# MCU_Power.net
KiCad netlist of a schematic drawn in Altium Designer
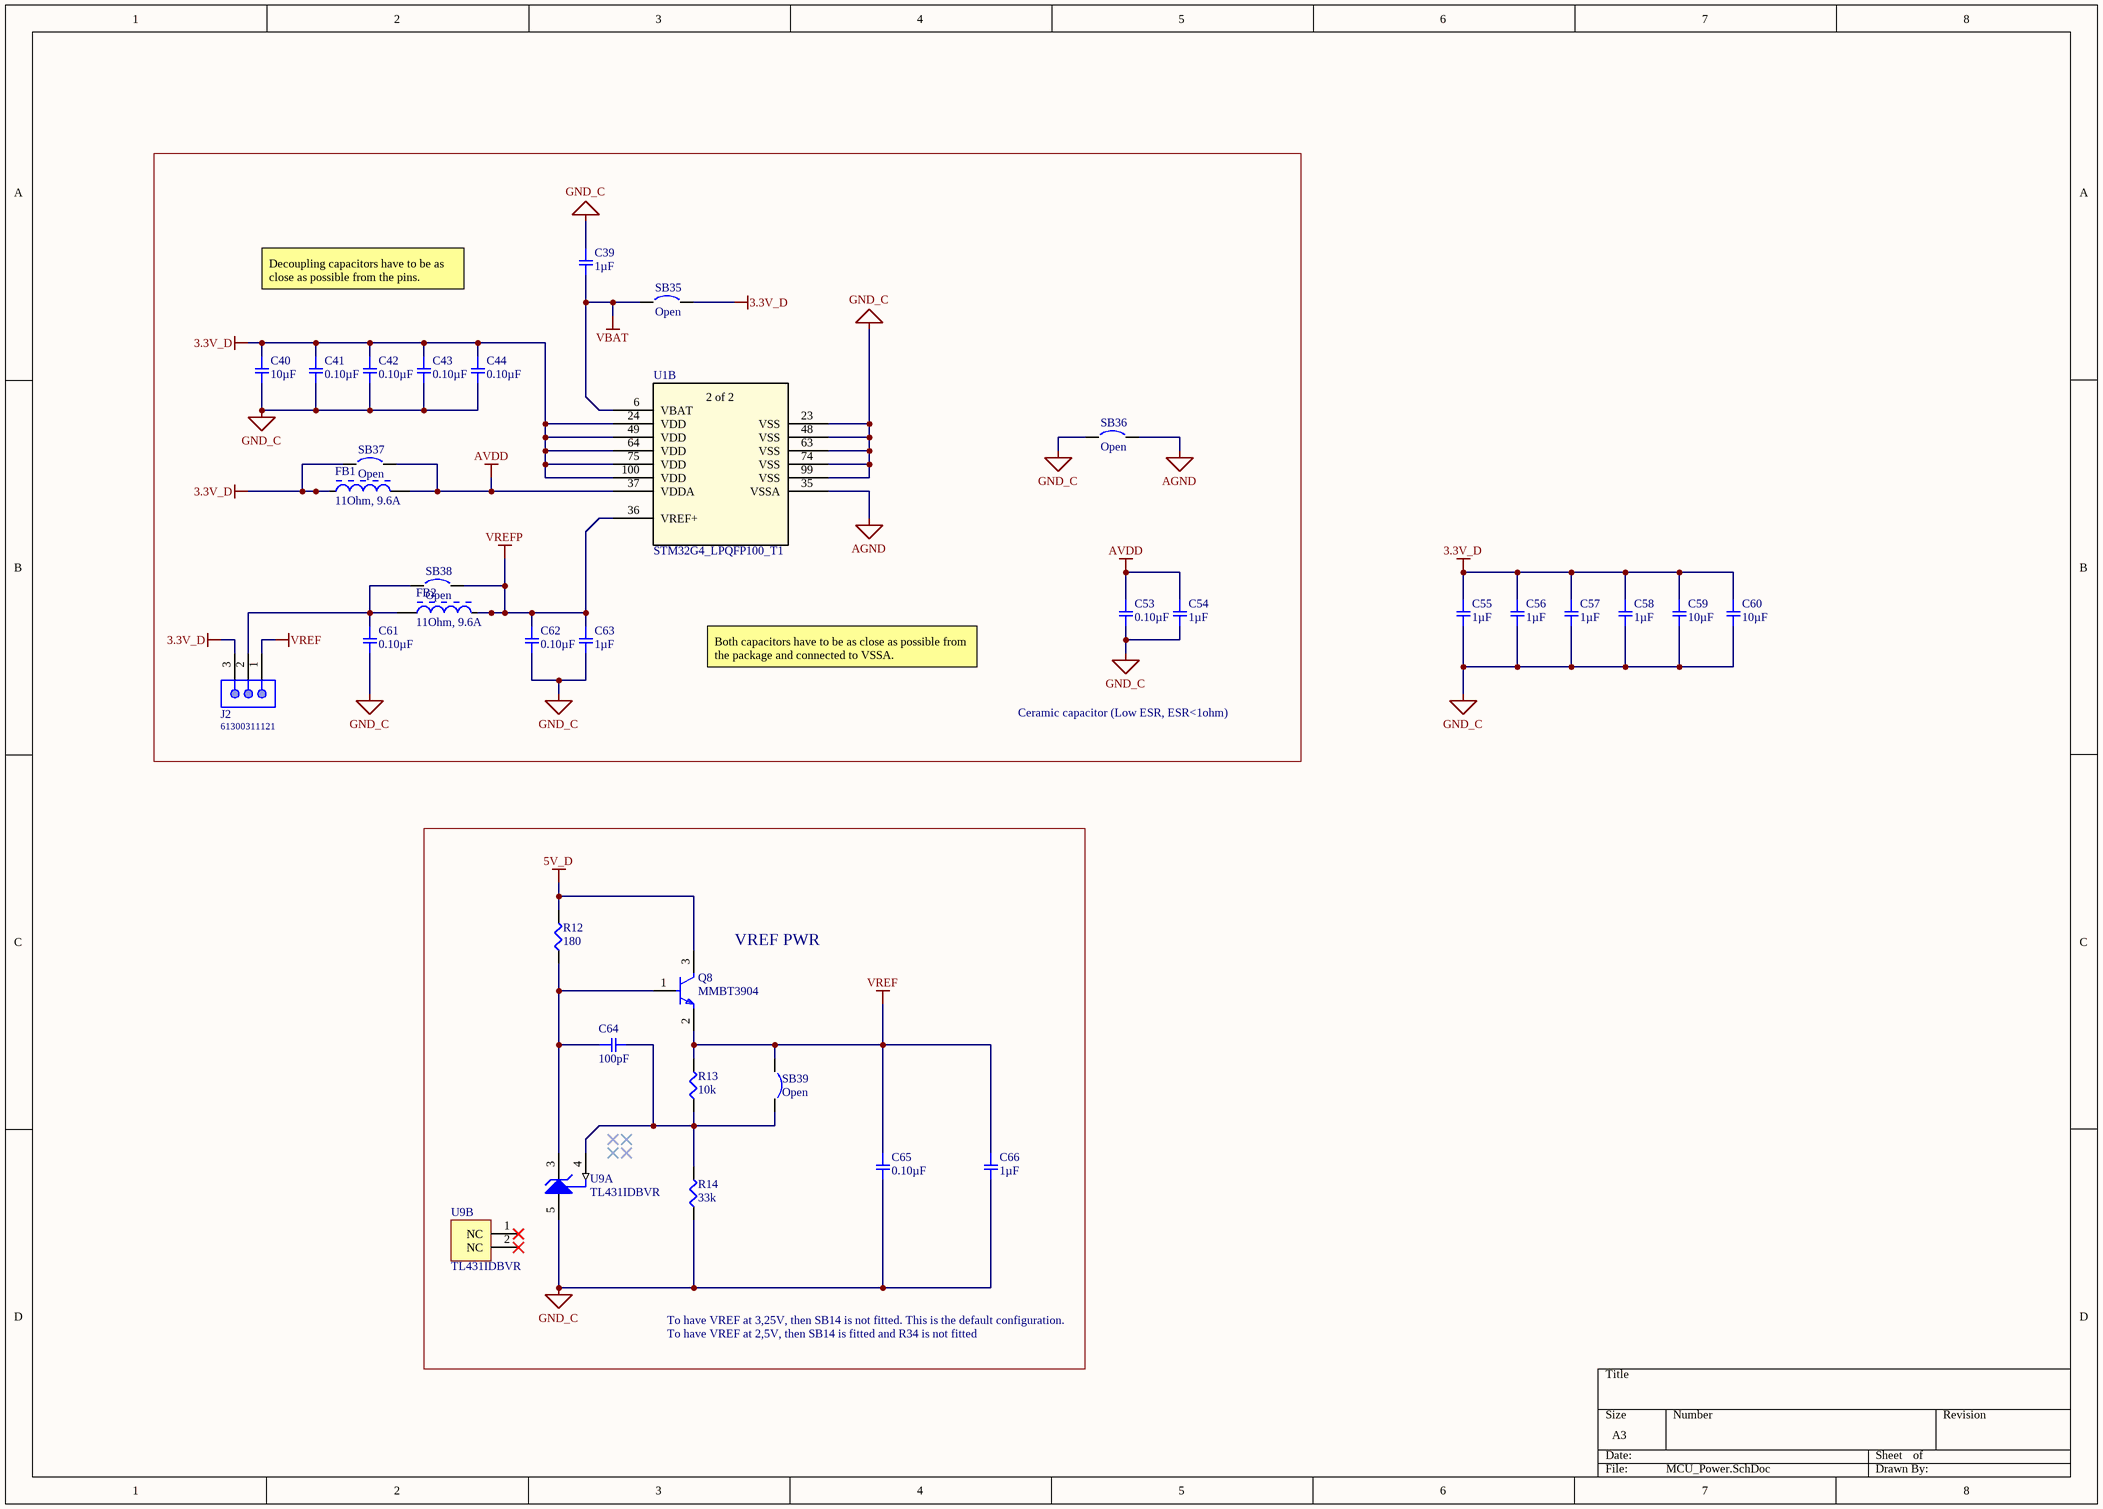
[diagram p0: MCU_Power.SchDoc]

(export (version "E")
  (design (tool "Eeschema 10.0.6"))
  (components
    (comp (ref "C39")
      (value "1µF")
      (footprint "SMD-0805C")
      (description "CAP CER 1UF 16V X7R 0805")
      (fields
        (field (name "DIGI-KEY PART NUMBER") "490-8043-1-ND")
        (field (name "PART NUMBER") "GCM219R71C105KA37D")
      )
      (libsource (lib "capacitor_murata_0805") (part "GCM219R71C105KA37D"))
    )
    (comp (ref "C40")
      (value "10µF")
      (footprint "SMD-0805C")
      (description "CAP CER 10UF 10V X7R 0805")
      (fields
        (field (name "DIGI-KEY PART NUMBER") "490-10674-1-ND")
        (field (name "PART NUMBER") "GCM21BR71A106KE22L")
      )
      (libsource (lib "capacitor_murata_0805") (part "GCM21BR71A106KE22L"))
    )
    (comp (ref "C41")
      (value "0.10µF")
      (footprint "SMD-0805C")
      (description "CAP CER 0.1UF 100V X7R 0805")
      (fields
        (field (name "DIGI-KEY PART NUMBER") "490-5825-1-ND")
        (field (name "PART NUMBER") "GCJ21BR72A104KA01L")
      )
      (libsource (lib "capacitor_murata_0805") (part "GCJ21BR72A104KA01L"))
    )
    (comp (ref "C42")
      (value "0.10µF")
      (footprint "SMD-0805C")
      (description "CAP CER 0.1UF 100V X7R 0805")
      (fields
        (field (name "DIGI-KEY PART NUMBER") "490-5825-1-ND")
        (field (name "PART NUMBER") "GCJ21BR72A104KA01L")
      )
      (libsource (lib "capacitor_murata_0805") (part "GCJ21BR72A104KA01L"))
    )
    (comp (ref "C43")
      (value "0.10µF")
      (footprint "SMD-0805C")
      (description "CAP CER 0.1UF 100V X7R 0805")
      (fields
        (field (name "DIGI-KEY PART NUMBER") "490-5825-1-ND")
        (field (name "PART NUMBER") "GCJ21BR72A104KA01L")
      )
      (libsource (lib "capacitor_murata_0805") (part "GCJ21BR72A104KA01L"))
    )
    (comp (ref "C44")
      (value "0.10µF")
      (footprint "SMD-0805C")
      (description "CAP CER 0.1UF 100V X7R 0805")
      (fields
        (field (name "DIGI-KEY PART NUMBER") "490-5825-1-ND")
        (field (name "PART NUMBER") "GCJ21BR72A104KA01L")
      )
      (libsource (lib "capacitor_murata_0805") (part "GCJ21BR72A104KA01L"))
    )
    (comp (ref "C53")
      (value "0.10µF")
      (footprint "SMD-0805C")
      (description "CAP CER 0.1UF 100V X7R 0805")
      (fields
        (field (name "DIGI-KEY PART NUMBER") "490-5825-1-ND")
        (field (name "PART NUMBER") "GCJ21BR72A104KA01L")
      )
      (libsource (lib "capacitor_murata_0805") (part "GCJ21BR72A104KA01L"))
    )
    (comp (ref "C54")
      (value "1µF")
      (footprint "SMD-0805C")
      (description "CAP CER 1UF 16V X7R 0805")
      (fields
        (field (name "DIGI-KEY PART NUMBER") "490-8043-1-ND")
        (field (name "PART NUMBER") "GCM219R71C105KA37D")
      )
      (libsource (lib "capacitor_murata_0805") (part "GCM219R71C105KA37D"))
    )
    (comp (ref "C55")
      (value "1µF")
      (footprint "SMD-0805C")
      (description "CAP CER 1UF 16V X7R 0805")
      (fields
        (field (name "DIGI-KEY PART NUMBER") "490-8043-1-ND")
        (field (name "PART NUMBER") "GCM219R71C105KA37D")
      )
      (libsource (lib "capacitor_murata_0805") (part "GCM219R71C105KA37D"))
    )
    (comp (ref "C56")
      (value "1µF")
      (footprint "SMD-0805C")
      (description "CAP CER 1UF 16V X7R 0805")
      (fields
        (field (name "DIGI-KEY PART NUMBER") "490-8043-1-ND")
        (field (name "PART NUMBER") "GCM219R71C105KA37D")
      )
      (libsource (lib "capacitor_murata_0805") (part "GCM219R71C105KA37D"))
    )
    (comp (ref "C57")
      (value "1µF")
      (footprint "SMD-0805C")
      (description "CAP CER 1UF 16V X7R 0805")
      (fields
        (field (name "DIGI-KEY PART NUMBER") "490-8043-1-ND")
        (field (name "PART NUMBER") "GCM219R71C105KA37D")
      )
      (libsource (lib "capacitor_murata_0805") (part "GCM219R71C105KA37D"))
    )
    (comp (ref "C58")
      (value "1µF")
      (footprint "SMD-0805C")
      (description "CAP CER 1UF 16V X7R 0805")
      (fields
        (field (name "DIGI-KEY PART NUMBER") "490-8043-1-ND")
        (field (name "PART NUMBER") "GCM219R71C105KA37D")
      )
      (libsource (lib "capacitor_murata_0805") (part "GCM219R71C105KA37D"))
    )
    (comp (ref "C59")
      (value "10µF")
      (footprint "SMD-0805C")
      (description "CAP CER 10UF 10V X7R 0805")
      (fields
        (field (name "DIGI-KEY PART NUMBER") "490-10674-1-ND")
        (field (name "PART NUMBER") "GCM21BR71A106KE22L")
      )
      (libsource (lib "capacitor_murata_0805") (part "GCM21BR71A106KE22L"))
    )
    (comp (ref "C60")
      (value "10µF")
      (footprint "SMD-0805C")
      (description "CAP CER 10UF 10V X7R 0805")
      (fields
        (field (name "DIGI-KEY PART NUMBER") "490-10674-1-ND")
        (field (name "PART NUMBER") "GCM21BR71A106KE22L")
      )
      (libsource (lib "capacitor_murata_0805") (part "GCM21BR71A106KE22L"))
    )
    (comp (ref "C61")
      (value "0.10µF")
      (footprint "SMD-0805C")
      (description "CAP CER 0.1UF 100V X7R 0805")
      (fields
        (field (name "DIGI-KEY PART NUMBER") "490-5825-1-ND")
        (field (name "PART NUMBER") "GCJ21BR72A104KA01L")
      )
      (libsource (lib "capacitor_murata_0805") (part "GCJ21BR72A104KA01L"))
    )
    (comp (ref "C62")
      (value "0.10µF")
      (footprint "SMD-0805C")
      (description "CAP CER 0.1UF 100V X7R 0805")
      (fields
        (field (name "DIGI-KEY PART NUMBER") "490-5825-1-ND")
        (field (name "PART NUMBER") "GCJ21BR72A104KA01L")
      )
      (libsource (lib "capacitor_murata_0805") (part "GCJ21BR72A104KA01L"))
    )
    (comp (ref "C63")
      (value "1µF")
      (footprint "SMD-0805C")
      (description "CAP CER 1UF 16V X7R 0805")
      (fields
        (field (name "DIGI-KEY PART NUMBER") "490-8043-1-ND")
        (field (name "PART NUMBER") "GCM219R71C105KA37D")
      )
      (libsource (lib "capacitor_murata_0805") (part "GCM219R71C105KA37D"))
    )
    (comp (ref "C64")
      (value "100pF")
      (footprint "SMD-0805C")
      (description "CAP CER 100PF 100V NP0 0805")
      (fields
        (field (name "DIGI-KEY PART NUMBER") "490-8036-1-ND")
        (field (name "PART NUMBER") "GCM2165C2A101JA16J")
      )
      (libsource (lib "capacitor_murata_0805") (part "GCM2165C2A101JA16J"))
    )
    (comp (ref "C65")
      (value "0.10µF")
      (footprint "SMD-0805C")
      (description "CAP CER 0.1UF 100V X7R 0805")
      (fields
        (field (name "DIGI-KEY PART NUMBER") "490-5825-1-ND")
        (field (name "PART NUMBER") "GCJ21BR72A104KA01L")
      )
      (libsource (lib "capacitor_murata_0805") (part "GCJ21BR72A104KA01L"))
    )
    (comp (ref "C66")
      (value "1µF")
      (footprint "SMD-0805C")
      (description "CAP CER 1UF 16V X7R 0805")
      (fields
        (field (name "DIGI-KEY PART NUMBER") "490-8043-1-ND")
        (field (name "PART NUMBER") "GCM219R71C105KA37D")
      )
      (libsource (lib "capacitor_murata_0805") (part "GCM219R71C105KA37D"))
    )
    (comp (ref "FB1")
      (value "11Ohm, 9.6A")
      (footprint "WE-CBF_0805_High Speed")
      (description "WE-CBF SMT EMI Suppression Ferrite Bead, size 0805, 11Ohm, 9.6A")
      (fields
        (field (name "MANUFACTURER PART NUMBER") "7427920")
        (field (name "MANUFACTURER") "Wurth Elektronik")
      )
      (libsource (lib "742792005_Altium_WE-CBF_rev20a") (part "7427920"))
    )
    (comp (ref "FB2")
      (value "11Ohm, 9.6A")
      (footprint "WE-CBF_0805_High Speed")
      (description "WE-CBF SMT EMI Suppression Ferrite Bead, size 0805, 11Ohm, 9.6A")
      (fields
        (field (name "MANUFACTURER PART NUMBER") "7427920")
        (field (name "MANUFACTURER") "Wurth Elektronik")
      )
      (libsource (lib "742792005_Altium_WE-CBF_rev20a") (part "7427920"))
    )
    (comp (ref "J2")
      (value "61300311121")
      (footprint "61300311121")
      (description "WR-PHD Pin Header, THT, pitch 2.54mm, Single Row, Vertical, 3pin")
      (fields (field (name "PUBLISHER") "Wurth Elektronik"))
      (libsource (lib "o155175v243 Altium_WR-PHD (rev19a)") (part "61300311121"))
    )
    (comp (ref "Q8")
      (value "MMBT3904")
      (footprint "FP-MA03D-MFG")
      (description "TRANS NPN 40V 0.2A SOT-23")
      (libsource (lib "Altium Content Vault") (part "b44e953556f554d0102664c7d152cb4"))
    )
    (comp (ref "R12")
      (value "180")
      (footprint "SMD-0603-RES")
      (description "RES SMD 180 OHM 1% 1/10W 0603")
      (fields (field (name "PART NUMBER") "ERJ-3EKF1800V") (field (name "DIGI-KEY PART NUMBER") "P180HCT-ND"))
      (libsource (lib "Panasonic_ERJ_0603") (part "ERJ-3EKF1800V"))
    )
    (comp (ref "R13")
      (value "10k")
      (footprint "SMD-0603-RES")
      (description "RES SMD 10K OHM 1% 1/10W 0603")
      (fields
        (field (name "PART NUMBER") "ERJ-3EKF1002V")
        (field (name "DIGI-KEY PART NUMBER") "P10.0KHCT-ND")
      )
      (libsource (lib "Panasonic_ERJ_0603") (part "ERJ-3EKF1002V"))
    )
    (comp (ref "R14")
      (value "33k")
      (footprint "SMD-0603-RES")
      (description "RES SMD 33K OHM 1% 1/10W 0603")
      (fields
        (field (name "PART NUMBER") "ERJ-3EKF3302V")
        (field (name "DIGI-KEY PART NUMBER") "P33.0KHCT-ND")
      )
      (libsource (lib "Panasonic_ERJ_0603") (part "ERJ-3EKF3302V"))
    )
    (comp (ref "SB35")
      (value "Open")
      (footprint "SB_0603")
      (description "Circuit Breaker")
      (fields (field (name "PUBLISHER") "Altium Limited"))
      (libsource (lib "Edge_Card_Ucc28951") (part "Solder Bridge"))
    )
    (comp (ref "SB36")
      (value "Open")
      (footprint "SB_0603")
      (description "Circuit Breaker")
      (fields (field (name "PUBLISHER") "Altium Limited"))
      (libsource (lib "Edge_Card_Ucc28951") (part "Solder Bridge"))
    )
    (comp (ref "SB37")
      (value "Open")
      (footprint "SB_0603")
      (description "Circuit Breaker")
      (fields (field (name "PUBLISHER") "Altium Limited"))
      (libsource (lib "Edge_Card_Ucc28951") (part "Solder Bridge"))
    )
    (comp (ref "SB38")
      (value "Open")
      (footprint "SB_0603")
      (description "Circuit Breaker")
      (fields (field (name "PUBLISHER") "Altium Limited"))
      (libsource (lib "Edge_Card_Ucc28951") (part "Solder Bridge"))
    )
    (comp (ref "SB39")
      (value "Open")
      (footprint "SB_0603")
      (description "Circuit Breaker")
      (fields (field (name "PUBLISHER") "Altium Limited"))
      (libsource (lib "Edge_Card_Ucc28951") (part "Solder Bridge"))
    )
    (comp (ref "U1")
      (value "STM32G4_LPQFP100_T1")
      (footprint "TSQFP50P1600X1600X160-100N")
      (description "No Description Available")
      (fields (field (name "COPYRIGHT") "Copyright (C) 2016 Accelerated Designs. All rights reserved"))
      (libsource (lib "Edge_Card_Ucc28951") (part "STM32G4_LPQFP100"))
    )
    (comp (ref "U9")
      (value "TL431IDBVR")
      (footprint "DBV0005A_M")
      (fields (field (name "MANUFACTURER") "Texas Instruments"))
      (libsource (lib "") (part "TI-TL431DBV5_1"))
    )
  )
  (nets
    (net (code "1") (name "3.3V_D") (class "Default")
      (node (ref "C40") (pin "1") (pinfunction "1_1") (pintype "passive"))
      (node (ref "C41") (pin "1") (pinfunction "1_1") (pintype "passive"))
      (node (ref "C42") (pin "1") (pinfunction "1_1") (pintype "passive"))
      (node (ref "C43") (pin "1") (pinfunction "1_1") (pintype "passive"))
      (node (ref "C44") (pin "1") (pinfunction "1_1") (pintype "passive"))
      (node (ref "C55") (pin "1") (pinfunction "1_1") (pintype "passive"))
      (node (ref "C56") (pin "1") (pinfunction "1_1") (pintype "passive"))
      (node (ref "C57") (pin "1") (pinfunction "1_1") (pintype "passive"))
      (node (ref "C58") (pin "1") (pinfunction "1_1") (pintype "passive"))
      (node (ref "C59") (pin "1") (pinfunction "1_1") (pintype "passive"))
      (node (ref "C60") (pin "1") (pinfunction "1_1") (pintype "passive"))
      (node (ref "FB1") (pin "1") (pinfunction "1_1") (pintype "passive"))
      (node (ref "J2") (pin "3") (pinfunction "3_3") (pintype "passive"))
      (node (ref "SB35") (pin "2") (pinfunction "2_2") (pintype "passive"))
      (node (ref "SB37") (pin "1") (pinfunction "1_1") (pintype "passive"))
      (node (ref "U1") (pin "100") (pinfunction "VDD_100") (pintype "power_in"))
      (node (ref "U1") (pin "24") (pinfunction "VDD_24") (pintype "power_in"))
      (node (ref "U1") (pin "49") (pinfunction "VDD_49") (pintype "power_in"))
      (node (ref "U1") (pin "64") (pinfunction "VDD_64") (pintype "power_in"))
      (node (ref "U1") (pin "75") (pinfunction "VDD_75") (pintype "power_in"))
    )
    (net (code "2") (name "5V_D") (class "Default")
      (node (ref "Q8") (pin "3") (pinfunction "C_3") (pintype "passive"))
      (node (ref "R12") (pin "2") (pinfunction "2_2") (pintype "passive"))
    )
    (net (code "3") (name "AGND") (class "Default")
      (node (ref "SB36") (pin "2") (pinfunction "2_2") (pintype "passive"))
      (node (ref "U1") (pin "35") (pinfunction "VSSA_35") (pintype "power_in"))
    )
    (net (code "4") (name "AVDD") (class "Default")
      (node (ref "C53") (pin "1") (pinfunction "1_1") (pintype "passive"))
      (node (ref "C54") (pin "1") (pinfunction "1_1") (pintype "passive"))
      (node (ref "FB1") (pin "2") (pinfunction "2_2") (pintype "passive"))
      (node (ref "SB37") (pin "2") (pinfunction "2_2") (pintype "passive"))
      (node (ref "U1") (pin "37") (pinfunction "VDDA_37") (pintype "power_in"))
    )
    (net (code "5") (name "GND_C") (class "Default")
      (node (ref "C39") (pin "1") (pinfunction "1_1") (pintype "passive"))
      (node (ref "C40") (pin "2") (pinfunction "2_2") (pintype "passive"))
      (node (ref "C41") (pin "2") (pinfunction "2_2") (pintype "passive"))
      (node (ref "C42") (pin "2") (pinfunction "2_2") (pintype "passive"))
      (node (ref "C43") (pin "2") (pinfunction "2_2") (pintype "passive"))
      (node (ref "C44") (pin "2") (pinfunction "2_2") (pintype "passive"))
      (node (ref "C53") (pin "2") (pinfunction "2_2") (pintype "passive"))
      (node (ref "C54") (pin "2") (pinfunction "2_2") (pintype "passive"))
      (node (ref "C55") (pin "2") (pinfunction "2_2") (pintype "passive"))
      (node (ref "C56") (pin "2") (pinfunction "2_2") (pintype "passive"))
      (node (ref "C57") (pin "2") (pinfunction "2_2") (pintype "passive"))
      (node (ref "C58") (pin "2") (pinfunction "2_2") (pintype "passive"))
      (node (ref "C59") (pin "2") (pinfunction "2_2") (pintype "passive"))
      (node (ref "C60") (pin "2") (pinfunction "2_2") (pintype "passive"))
      (node (ref "C61") (pin "2") (pinfunction "2_2") (pintype "passive"))
      (node (ref "C62") (pin "2") (pinfunction "2_2") (pintype "passive"))
      (node (ref "C63") (pin "2") (pinfunction "2_2") (pintype "passive"))
      (node (ref "C65") (pin "2") (pinfunction "2_2") (pintype "passive"))
      (node (ref "C66") (pin "2") (pinfunction "2_2") (pintype "passive"))
      (node (ref "R14") (pin "1") (pinfunction "1_1") (pintype "passive"))
      (node (ref "SB36") (pin "1") (pinfunction "1_1") (pintype "passive"))
      (node (ref "U1") (pin "23") (pinfunction "VSS_23") (pintype "power_in"))
      (node (ref "U1") (pin "48") (pinfunction "VSS_48") (pintype "power_in"))
      (node (ref "U1") (pin "63") (pinfunction "VSS_63") (pintype "power_in"))
      (node (ref "U1") (pin "74") (pinfunction "VSS_74") (pintype "power_in"))
      (node (ref "U1") (pin "99") (pinfunction "VSS_99") (pintype "power_in"))
      (node (ref "U9") (pin "5") (pinfunction "ANODE_5") (pintype "passive"))
    )
    (net (code "6") (name "Net-(C61-Pad1)") (class "Default")
      (node (ref "C61") (pin "1") (pinfunction "1_1") (pintype "passive"))
      (node (ref "FB2") (pin "1") (pinfunction "1_1") (pintype "passive"))
      (node (ref "J2") (pin "2") (pinfunction "2_2") (pintype "passive"))
      (node (ref "SB38") (pin "1") (pinfunction "1_1") (pintype "passive"))
    )
    (net (code "7") (name "Net-(Q8-B)") (class "Default")
      (node (ref "C64") (pin "1") (pinfunction "1_1") (pintype "passive"))
      (node (ref "Q8") (pin "1") (pinfunction "B_1") (pintype "passive"))
      (node (ref "R12") (pin "1") (pinfunction "1_1") (pintype "passive"))
      (node (ref "U9") (pin "3") (pinfunction "CATHODE_3") (pintype "passive"))
    )
    (net (code "8") (name "Net-(U9A-REF)") (class "Default")
      (node (ref "C64") (pin "2") (pinfunction "2_2") (pintype "passive"))
      (node (ref "R13") (pin "1") (pinfunction "1_1") (pintype "passive"))
      (node (ref "R14") (pin "2") (pinfunction "2_2") (pintype "passive"))
      (node (ref "SB39") (pin "2") (pinfunction "2_2") (pintype "passive"))
      (node (ref "U9") (pin "4") (pinfunction "REF_4") (pintype "input"))
    )
    (net (code "9") (name "VBAT") (class "Default")
      (node (ref "C39") (pin "2") (pinfunction "2_2") (pintype "passive"))
      (node (ref "SB35") (pin "1") (pinfunction "1_1") (pintype "passive"))
      (node (ref "U1") (pin "6") (pinfunction "VBAT_6") (pintype "power_in"))
    )
    (net (code "10") (name "VREF") (class "Default")
      (node (ref "C65") (pin "1") (pinfunction "1_1") (pintype "passive"))
      (node (ref "C66") (pin "1") (pinfunction "1_1") (pintype "passive"))
      (node (ref "J2") (pin "1") (pinfunction "1_1") (pintype "passive"))
      (node (ref "Q8") (pin "2") (pinfunction "E_2") (pintype "passive"))
      (node (ref "R13") (pin "2") (pinfunction "2_2") (pintype "passive"))
      (node (ref "SB39") (pin "1") (pinfunction "1_1") (pintype "passive"))
    )
    (net (code "11") (name "VREFP") (class "Default")
      (node (ref "C62") (pin "1") (pinfunction "1_1") (pintype "passive"))
      (node (ref "C63") (pin "1") (pinfunction "1_1") (pintype "passive"))
      (node (ref "FB2") (pin "2") (pinfunction "2_2") (pintype "passive"))
      (node (ref "SB38") (pin "2") (pinfunction "2_2") (pintype "passive"))
      (node (ref "U1") (pin "36") (pinfunction "VREF+_36") (pintype "power_in"))
    )
    (net (code "12") (name "unconnected-(U9B-NC-Pad1)") (class "Default")
      (node (ref "U9") (pin "1") (pinfunction "NC_1") (pintype "passive+no_connect"))
    )
    (net (code "13") (name "unconnected-(U9B-NC-Pad2)") (class "Default")
      (node (ref "U9") (pin "2") (pinfunction "NC_2") (pintype "passive+no_connect"))
    )
  )
)
